# 11_-_POWER.net
KiCad netlist of a schematic drawn in Altium Designer
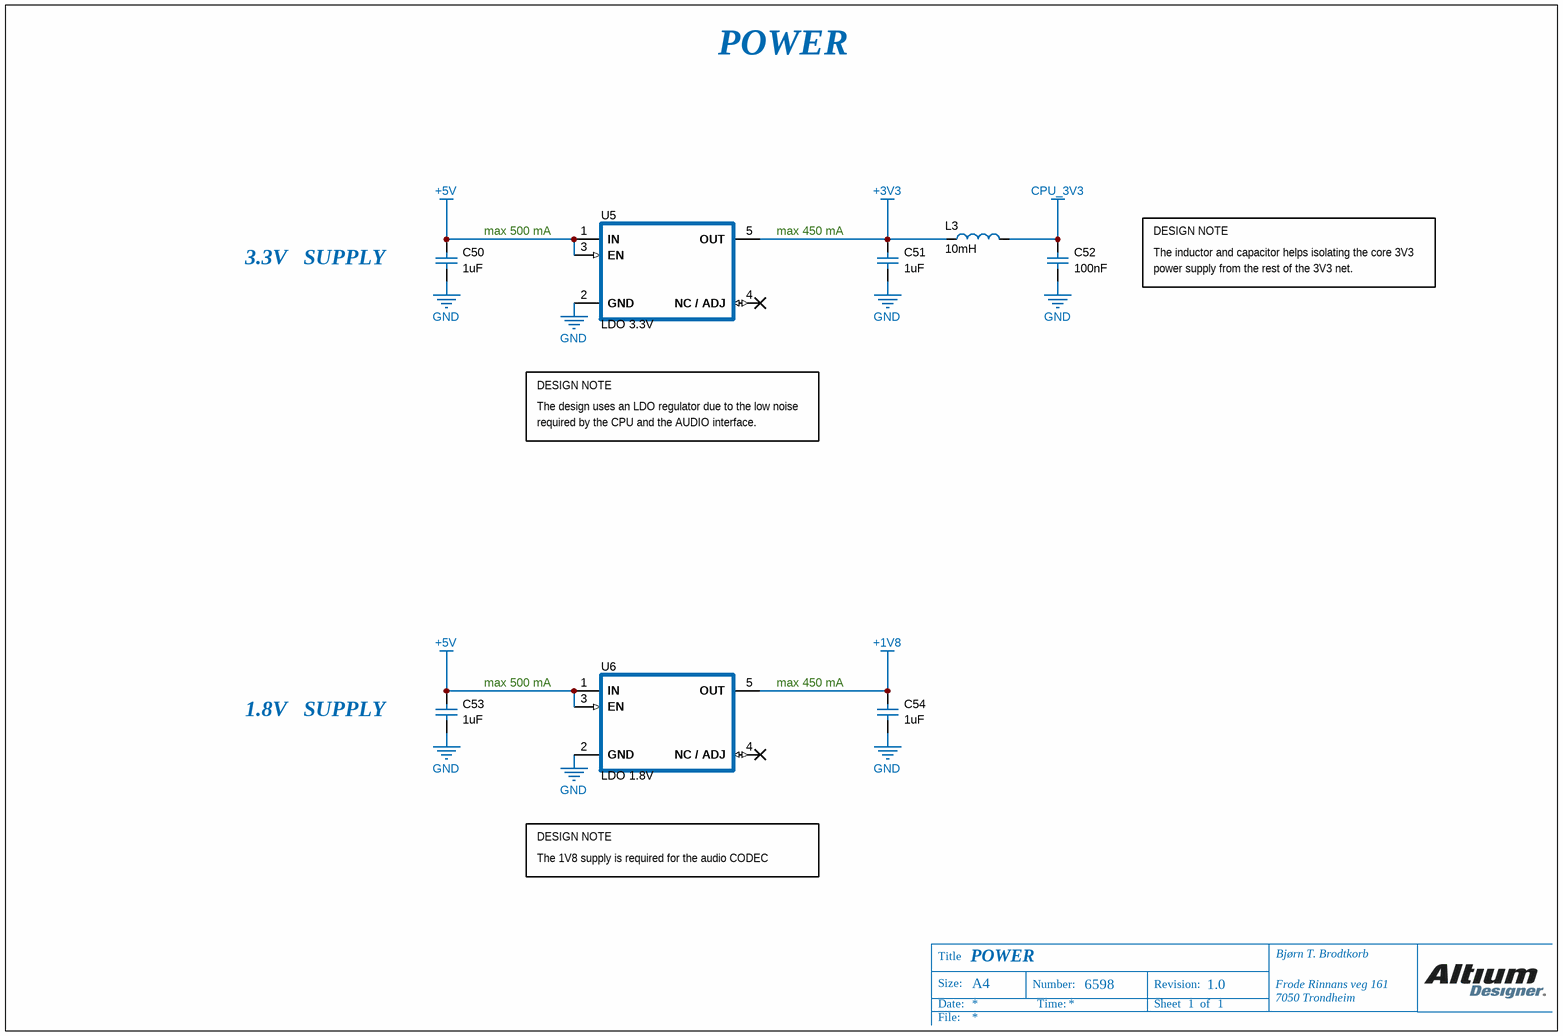
[diagram p0: [11] - POWER.SchDoc]

(export (version "E")
  (design (tool "Eeschema 10.0.6"))
  (components
    (comp (ref "C50")
      (value "1uF")
      (footprint "C0805")
      (description "C0805")
      (fields (field (name "Comment") "08053C105KAT2A"))
      (libsource (lib "Passive components") (part "08053C105KAT2A"))
    )
    (comp (ref "C51")
      (value "1uF")
      (footprint "C0805")
      (description "C0805")
      (fields (field (name "Comment") "08053C105KAT2A"))
      (libsource (lib "Passive components") (part "08053C105KAT2A"))
    )
    (comp (ref "C52")
      (value "100nF")
      (footprint "C0603")
      (description "C0603")
      (fields (field (name "Comment") "02016D104KAT2A"))
      (libsource (lib "Passive components") (part "02016D104KAT2A"))
    )
    (comp (ref "C53")
      (value "1uF")
      (footprint "C0805")
      (description "C0805")
      (fields (field (name "Comment") "08053C105KAT2A"))
      (libsource (lib "Passive components") (part "08053C105KAT2A"))
    )
    (comp (ref "C54")
      (value "1uF")
      (footprint "C0805")
      (description "C0805")
      (fields (field (name "Comment") "08053C105KAT2A"))
      (libsource (lib "Passive components") (part "08053C105KAT2A"))
    )
    (comp (ref "L3")
      (value "10mH")
      (footprint "Inductor 0603")
      (description "Inductor 0603")
      (fields (field (name "Comment") "MLZ1608A2R2WT"))
      (libsource (lib "Passive components") (part "MLZ1608A2R2WT"))
    )
    (comp (ref "U5")
      (value "LDO 3.3V")
      (footprint "NCV8161BSN330T1G")
      (description "LDO fixed 3.3V 450mA ultra-low noise")
      (libsource (lib "Voltage regulators") (part "NCV8161BSN330T1G"))
    )
    (comp (ref "U6")
      (value "LDO 1.8V")
      (footprint "SOT95P275X110-5N")
      (description "LDO fixed 1.8V 450mA ultra-low noise")
      (libsource (lib "Voltage regulators") (part "NCV8161ASN180T1G"))
    )
  )
  (nets
    (net (code "1") (name "+1V8") (class "Default")
      (node (ref "C54") (pin "2") (pinfunction "2_2") (pintype "passive"))
      (node (ref "U6") (pin "5") (pinfunction "OUT_5") (pintype "power_in"))
    )
    (net (code "2") (name "+3V3") (class "Default")
      (node (ref "C51") (pin "2") (pinfunction "2_2") (pintype "passive"))
      (node (ref "L3") (pin "1") (pinfunction "1_1") (pintype "passive"))
      (node (ref "U5") (pin "5") (pinfunction "OUT_5") (pintype "power_in"))
    )
    (net (code "3") (name "+5V") (class "Default")
      (node (ref "C50") (pin "2") (pinfunction "2_2") (pintype "passive"))
      (node (ref "C53") (pin "2") (pinfunction "2_2") (pintype "passive"))
      (node (ref "U5") (pin "1") (pinfunction "IN_1") (pintype "power_in"))
      (node (ref "U5") (pin "3") (pinfunction "EN_3") (pintype "input"))
      (node (ref "U6") (pin "1") (pinfunction "IN_1") (pintype "power_in"))
      (node (ref "U6") (pin "3") (pinfunction "EN_3") (pintype "input"))
    )
    (net (code "4") (name "CPU_3V3") (class "Default")
      (node (ref "C52") (pin "2") (pinfunction "2_2") (pintype "passive"))
      (node (ref "L3") (pin "2") (pinfunction "2_2") (pintype "passive"))
    )
    (net (code "5") (name "GND") (class "Default")
      (node (ref "C50") (pin "1") (pinfunction "1_1") (pintype "passive"))
      (node (ref "C51") (pin "1") (pinfunction "1_1") (pintype "passive"))
      (node (ref "C52") (pin "1") (pinfunction "1_1") (pintype "passive"))
      (node (ref "C53") (pin "1") (pinfunction "1_1") (pintype "passive"))
      (node (ref "C54") (pin "1") (pinfunction "1_1") (pintype "passive"))
      (node (ref "U5") (pin "2") (pinfunction "GND_2") (pintype "power_in"))
      (node (ref "U6") (pin "2") (pinfunction "GND_2") (pintype "power_in"))
    )
    (net (code "6") (name "unconnected-(U5-NC_{slash}_ADJ-Pad4)") (class "Default")
      (node (ref "U5") (pin "4") (pinfunction "NC_/_ADJ_4") (pintype "bidirectional+no_connect"))
    )
    (net (code "7") (name "unconnected-(U6-NC_{slash}_ADJ-Pad4)") (class "Default")
      (node (ref "U6") (pin "4") (pinfunction "NC_/_ADJ_4") (pintype "bidirectional+no_connect"))
    )
  )
)
